# RAMPSdisplay.net
KiCad netlist of a schematic drawn in EAGLE
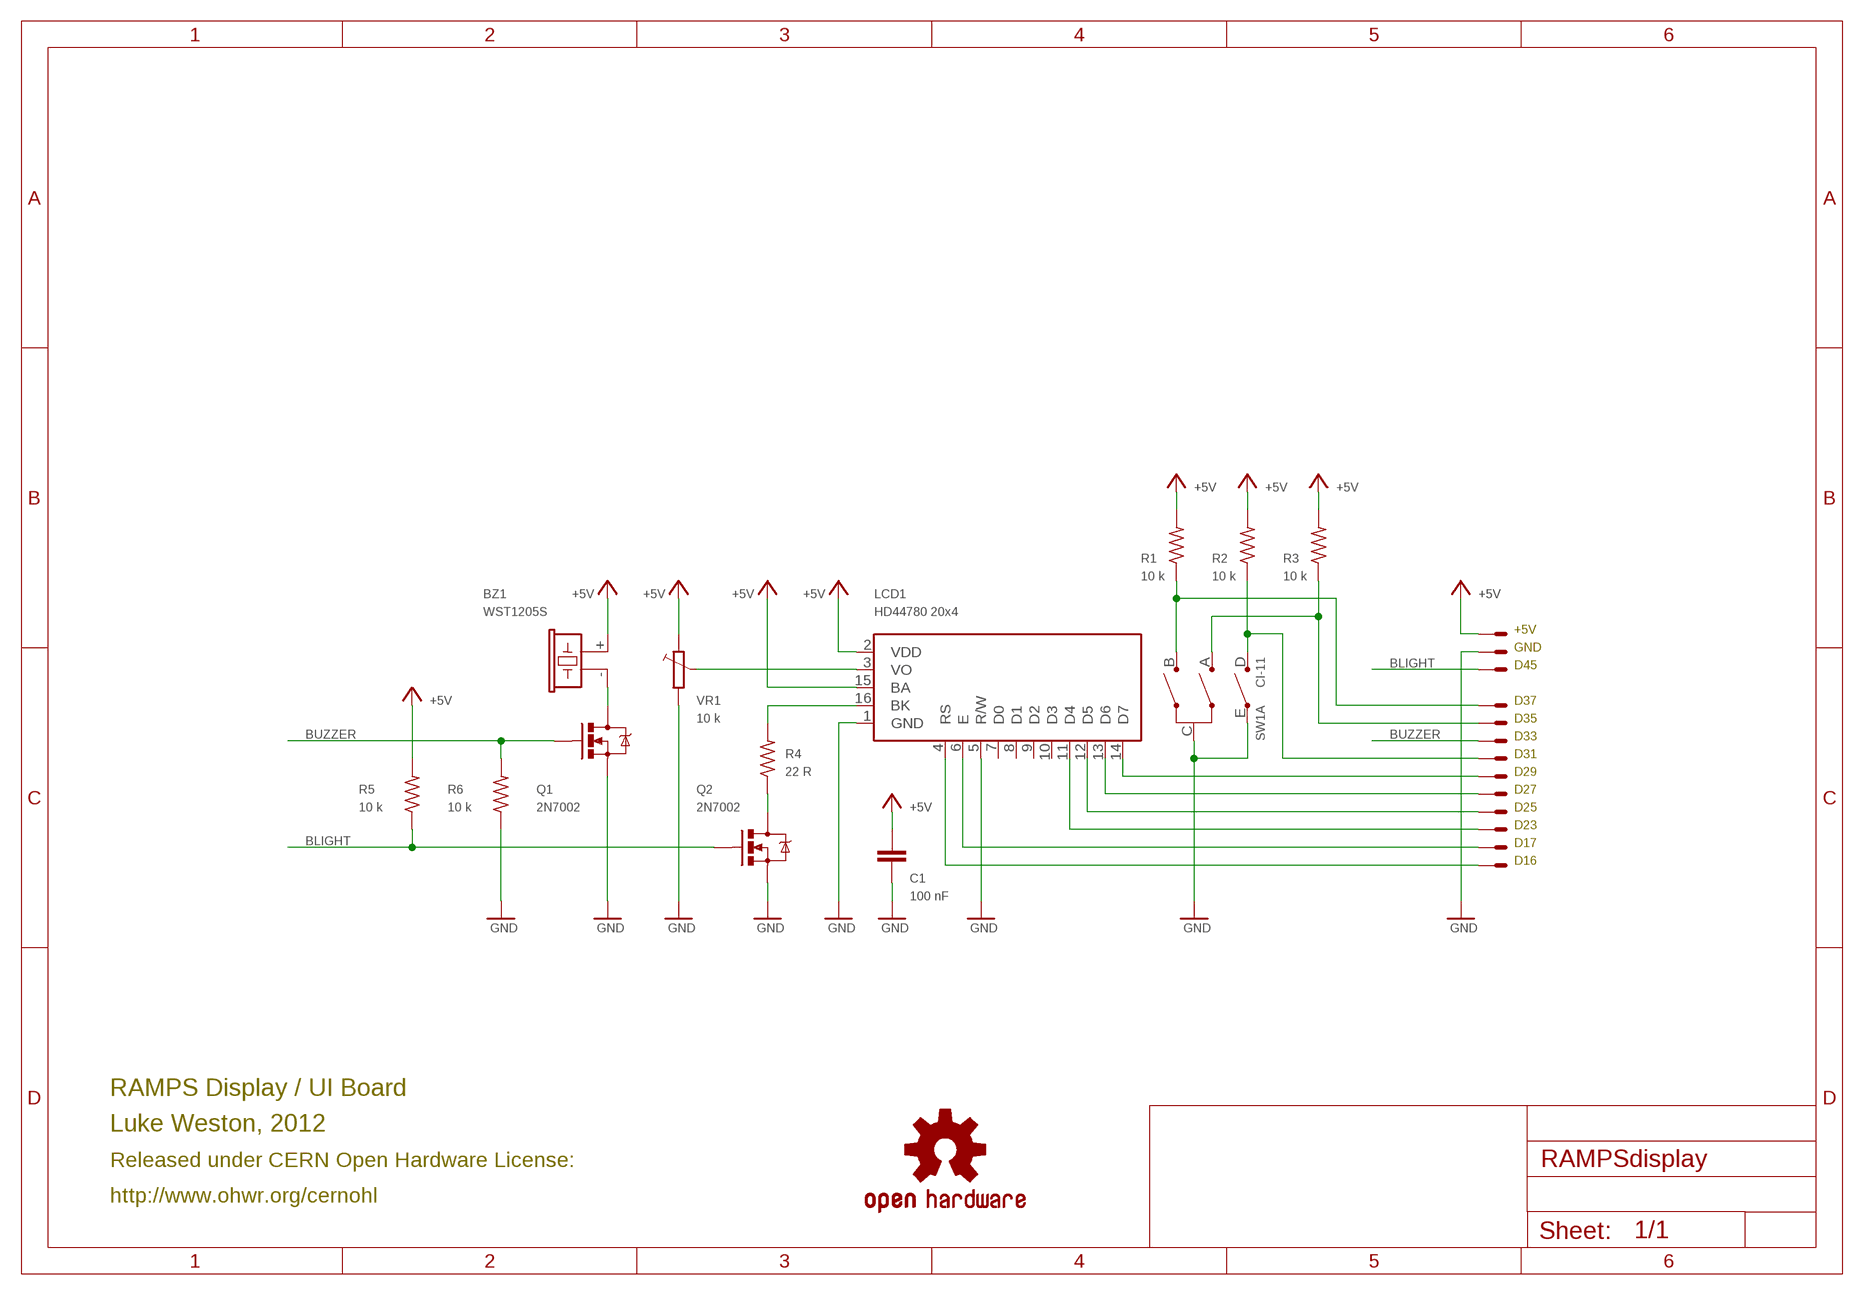
[diagram p0: schematic, sheet 1]

(export (version "E")
  (design (tool "Eeschema 10.0.6"))
  (components
    (comp (ref "BZ1")
      (value "WST1205S")
      (footprint "eagle-import:F_CM12P")
      (libsource (lib "eagle-import") (part "F/CM12P"))
    )
    (comp (ref "C1")
      (value "100 nF")
      (footprint "eagle-import:C0805K")
      (libsource (lib "eagle-import") (part "C-EUC0805K"))
    )
    (comp (ref "J1")
      (value "22-05-7038-03")
      (footprint "eagle-import:7395-03")
      (libsource (lib "eagle-import") (part "22-?-0305-7038"))
    )
    (comp (ref "J2")
      (value "22-05-7108-10")
      (footprint "eagle-import:7395-10")
      (libsource (lib "eagle-import") (part "22-?-1005-7108"))
    )
    (comp (ref "LCD1")
      (value "HD44780 20x4")
      (footprint "eagle-import:HDM20416L")
      (libsource (lib "eagle-import") (part "HDM20416L"))
    )
    (comp (ref "Q1")
      (value "2N7002")
      (footprint "eagle-import:SOT23-3")
      (libsource (lib "eagle-import") (part "MOSFET-NCHANNELSMD"))
    )
    (comp (ref "Q2")
      (value "2N7002")
      (footprint "eagle-import:SOT23-3")
      (libsource (lib "eagle-import") (part "MOSFET-NCHANNELSMD"))
    )
    (comp (ref "R1")
      (value "10 k")
      (footprint "eagle-import:M0805")
      (libsource (lib "eagle-import") (part "R-US_M0805"))
    )
    (comp (ref "R2")
      (value "10 k")
      (footprint "eagle-import:M0805")
      (libsource (lib "eagle-import") (part "R-US_M0805"))
    )
    (comp (ref "R3")
      (value "10 k")
      (footprint "eagle-import:M0805")
      (libsource (lib "eagle-import") (part "R-US_M0805"))
    )
    (comp (ref "R4")
      (value "22 R")
      (footprint "eagle-import:M0805")
      (libsource (lib "eagle-import") (part "R-US_M0805"))
    )
    (comp (ref "R5")
      (value "10 k")
      (footprint "eagle-import:M0805")
      (libsource (lib "eagle-import") (part "R-US_M0805"))
    )
    (comp (ref "R6")
      (value "10 k")
      (footprint "eagle-import:M0805")
      (libsource (lib "eagle-import") (part "R-US_M0805"))
    )
    (comp (ref "SW1")
      (value "CI-11")
      (footprint "eagle-import:CI-11")
      (libsource (lib "eagle-import") (part "CI-11"))
    )
    (comp (ref "U$")
      (value "OSHW-LOGOS")
      (footprint "eagle-import:OSHW-LOGO-S")
      (libsource (lib "eagle-import") (part "OSHW-LOGOS"))
    )
    (comp (ref "VR1")
      (value "10 k")
      (footprint "eagle-import:S64W")
      (libsource (lib "eagle-import") (part "TRIM_EU-S64W"))
    )
  )
  (nets
    (net (code "1") (name "+5V") (class "Default")
      (node (ref "BZ1") (pin "+") (pinfunction "1_+") (pintype "passive"))
      (node (ref "C1") (pin "1") (pinfunction "1_1") (pintype "passive"))
      (node (ref "J1") (pin "1") (pinfunction "S_1") (pintype "passive"))
      (node (ref "LCD1") (pin "15") (pinfunction "BA_15") (pintype "bidirectional"))
      (node (ref "LCD1") (pin "2") (pinfunction "VDD_2") (pintype "bidirectional"))
      (node (ref "R1") (pin "2") (pinfunction "2_2") (pintype "passive"))
      (node (ref "R2") (pin "2") (pinfunction "2_2") (pintype "passive"))
      (node (ref "R3") (pin "2") (pinfunction "2_2") (pintype "passive"))
      (node (ref "R5") (pin "2") (pinfunction "2_2") (pintype "passive"))
      (node (ref "VR1") (pin "E") (pinfunction "E_E") (pintype "passive"))
    )
    (net (code "2") (name "/BLIGHT") (class "Default")
      (node (ref "J1") (pin "3") (pinfunction "S_3") (pintype "passive"))
      (node (ref "Q2") (pin "1") (pinfunction "G_1") (pintype "passive"))
      (node (ref "R5") (pin "1") (pinfunction "1_1") (pintype "passive"))
    )
    (net (code "3") (name "/BUZZER") (class "Default")
      (node (ref "J2") (pin "3") (pinfunction "S_3") (pintype "passive"))
      (node (ref "Q1") (pin "1") (pinfunction "G_1") (pintype "passive"))
      (node (ref "R6") (pin "2") (pinfunction "2_2") (pintype "passive"))
    )
    (net (code "4") (name "GND") (class "Default")
      (node (ref "C1") (pin "2") (pinfunction "2_2") (pintype "passive"))
      (node (ref "J1") (pin "2") (pinfunction "S_2") (pintype "passive"))
      (node (ref "LCD1") (pin "1") (pinfunction "GND_1") (pintype "bidirectional"))
      (node (ref "LCD1") (pin "5") (pinfunction "R/W_5") (pintype "bidirectional"))
      (node (ref "Q1") (pin "2") (pinfunction "S_2") (pintype "passive"))
      (node (ref "Q2") (pin "2") (pinfunction "S_2") (pintype "passive"))
      (node (ref "R6") (pin "1") (pinfunction "1_1") (pintype "passive"))
      (node (ref "SW1") (pin "C") (pinfunction "C_C") (pintype "passive"))
      (node (ref "SW1") (pin "E") (pinfunction "E_E") (pintype "passive"))
      (node (ref "VR1") (pin "A") (pinfunction "A_A") (pintype "passive"))
    )
    (net (code "5") (name "Net-(BZ1-2)") (class "Default")
      (node (ref "BZ1") (pin "-") (pinfunction "2_-") (pintype "passive"))
      (node (ref "Q1") (pin "3") (pinfunction "D_3") (pintype "passive"))
    )
    (net (code "6") (name "Net-(J2A-S)") (class "Default")
      (node (ref "J2") (pin "1") (pinfunction "S_1") (pintype "passive"))
      (node (ref "R1") (pin "1") (pinfunction "1_1") (pintype "passive"))
      (node (ref "SW1") (pin "B") (pinfunction "B_B") (pintype "passive"))
    )
    (net (code "7") (name "Net-(J2B-S)") (class "Default")
      (node (ref "J2") (pin "10") (pinfunction "S_10") (pintype "passive"))
      (node (ref "LCD1") (pin "4") (pinfunction "RS_4") (pintype "bidirectional"))
    )
    (net (code "8") (name "Net-(J2C-S)") (class "Default")
      (node (ref "J2") (pin "2") (pinfunction "S_2") (pintype "passive"))
      (node (ref "R3") (pin "1") (pinfunction "1_1") (pintype "passive"))
      (node (ref "SW1") (pin "A") (pinfunction "A_A") (pintype "passive"))
    )
    (net (code "9") (name "Net-(J2E-S)") (class "Default")
      (node (ref "J2") (pin "4") (pinfunction "S_4") (pintype "passive"))
      (node (ref "R2") (pin "1") (pinfunction "1_1") (pintype "passive"))
      (node (ref "SW1") (pin "D") (pinfunction "D_D") (pintype "passive"))
    )
    (net (code "10") (name "Net-(J2F-S)") (class "Default")
      (node (ref "J2") (pin "5") (pinfunction "S_5") (pintype "passive"))
      (node (ref "LCD1") (pin "14") (pinfunction "D7_14") (pintype "bidirectional"))
    )
    (net (code "11") (name "Net-(J2G-S)") (class "Default")
      (node (ref "J2") (pin "6") (pinfunction "S_6") (pintype "passive"))
      (node (ref "LCD1") (pin "13") (pinfunction "D6_13") (pintype "bidirectional"))
    )
    (net (code "12") (name "Net-(J2H-S)") (class "Default")
      (node (ref "J2") (pin "7") (pinfunction "S_7") (pintype "passive"))
      (node (ref "LCD1") (pin "12") (pinfunction "D5_12") (pintype "bidirectional"))
    )
    (net (code "13") (name "Net-(J2I-S)") (class "Default")
      (node (ref "J2") (pin "8") (pinfunction "S_8") (pintype "passive"))
      (node (ref "LCD1") (pin "11") (pinfunction "D4_11") (pintype "bidirectional"))
    )
    (net (code "14") (name "Net-(J2J-S)") (class "Default")
      (node (ref "J2") (pin "9") (pinfunction "S_9") (pintype "passive"))
      (node (ref "LCD1") (pin "6") (pinfunction "E_6") (pintype "bidirectional"))
    )
    (net (code "15") (name "Net-(LCD1-BK)") (class "Default")
      (node (ref "LCD1") (pin "16") (pinfunction "BK_16") (pintype "bidirectional"))
      (node (ref "R4") (pin "2") (pinfunction "2_2") (pintype "passive"))
    )
    (net (code "16") (name "Net-(LCD1-VO)") (class "Default")
      (node (ref "LCD1") (pin "3") (pinfunction "VO_3") (pintype "bidirectional"))
      (node (ref "VR1") (pin "S") (pinfunction "S_S") (pintype "passive"))
    )
    (net (code "17") (name "Net-(Q2-D)") (class "Default")
      (node (ref "Q2") (pin "3") (pinfunction "D_3") (pintype "passive"))
      (node (ref "R4") (pin "1") (pinfunction "1_1") (pintype "passive"))
    )
    (net (code "18") (name "unconnected-(LCD1-D0-Pad7)") (class "Default")
      (node (ref "LCD1") (pin "7") (pinfunction "D0_7") (pintype "bidirectional"))
    )
    (net (code "19") (name "unconnected-(LCD1-D1-Pad8)") (class "Default")
      (node (ref "LCD1") (pin "8") (pinfunction "D1_8") (pintype "bidirectional"))
    )
    (net (code "20") (name "unconnected-(LCD1-D2-Pad9)") (class "Default")
      (node (ref "LCD1") (pin "9") (pinfunction "D2_9") (pintype "bidirectional"))
    )
    (net (code "21") (name "unconnected-(LCD1-D3-Pad10)") (class "Default")
      (node (ref "LCD1") (pin "10") (pinfunction "D3_10") (pintype "bidirectional"))
    )
  )
)
